# PowerSupply.net
KiCad netlist of a schematic drawn in Altium Designer
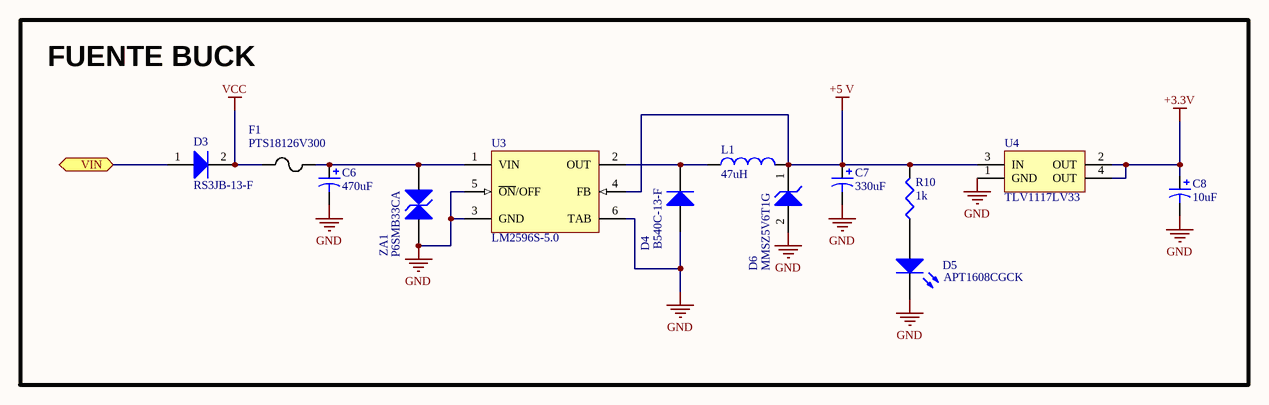
[diagram p0: PowerSupply.SchDoc]

(export (version "E")
  (design (tool "Eeschema 10.0.6"))
  (components
    (comp (ref "C6")
      (value "470uF")
      (footprint "CapElecSMD_10mm")
      (description "Polarized Capacitor (Surface Mount)")
      (fields (field (name "PUBLISHER") "Altium Limited"))
      (libsource (lib "Miscellaneous Devices") (part "Cap Pol3"))
    )
    (comp (ref "C7")
      (value "330uF")
      (footprint "CapElecSMD_8mm")
      (description "Polarized Capacitor (Surface Mount)")
      (fields (field (name "PUBLISHER") "Altium Limited"))
      (libsource (lib "Miscellaneous Devices") (part "Cap Pol3"))
    )
    (comp (ref "C8")
      (value "10uF")
      (footprint "CAPC3225N")
      (description "Polarized Capacitor (Surface Mount)")
      (fields (field (name "PUBLISHER") "Altium Limited"))
      (libsource (lib "Miscellaneous Devices") (part "Cap Pol3"))
    )
    (comp (ref "D3")
      (value "RS3JB-13-F")
      (footprint "MH_Miscellaneous_Devices_Pcblib:SMB")
      (description "Default Diode")
      (fields (field (name "PUBLISHER") "Altium Limited"))
      (libsource (lib "") (part "Diode_1"))
    )
    (comp (ref "D4")
      (value "B540C-13-F")
      (footprint "MH_Miscellaneous_Devices_Pcblib:SMC")
      (description "Default Diode")
      (fields (field (name "PUBLISHER") "Altium Limited"))
      (libsource (lib "Miscellaneous Devices") (part "Diode"))
    )
    (comp (ref "D5")
      (value "APT1608CGCK")
      (footprint "ChipDiode1608")
      (description "LED 1.6x0.8 mm 570 nm GRN CLR SMD")
      (fields (field (name "PUBLISHER") "Altium Limited"))
      (libsource (lib "Miscellaneous Devices") (part "LED2"))
    )
    (comp (ref "D6")
      (value "MMSZ5V6T1G")
      (footprint "SOD-123_ONS-M")
      (description "Zener Diode")
      (fields (field (name "PUBLISHER") "Altium Limited"))
      (libsource (lib "Miscellaneous Devices") (part "D Zener"))
    )
    (comp (ref "F1")
      (value "PTS18126V300")
      (footprint "FUSE_PTS18126_COB")
      (description "PTC RESET FUSE 6V 3A 1812")
      (libsource (lib "Adox_Lib") (part "PTS18126V300"))
    )
    (comp (ref "L1")
      (value "47uH")
      (footprint "INDUCTOR_47UH_3A")
      (description "Inductor")
      (fields (field (name "PUBLISHER") "Altium Limited"))
      (libsource (lib "Miscellaneous Devices") (part "Inductor"))
    )
    (comp (ref "R10")
      (value "1k")
      (footprint "RESC2012N")
      (description "Resistor")
      (fields (field (name "PUBLISHER") "Altium Limited"))
      (libsource (lib "Miscellaneous Devices") (part "Res3"))
    )
    (comp (ref "U3")
      (value "LM2596S-5.0")
      (footprint "LM2596S-5.0")
      (description "IC REG BUCK 5V 3A TO263-5L")
      (libsource (lib "MH_Lib") (part "LM2596S-5.0"))
    )
    (comp (ref "U4")
      (value "TLV1117LV33")
      (footprint "SOT223")
      (description "1-A, Positive Fixed Voltage, Low-Dropout Regulator")
      (libsource (lib "Adox_Lib") (part "TLV1117LV33"))
    )
    (comp (ref "ZA1")
      (value "P6SMB33CA")
      (footprint "MH_Miscellaneous_Devices_Pcblib:SMB")
      (description "Transient voltage suppressor diode")
      (libsource (lib "Adox_Lib") (part "TVS Diode"))
    )
  )
  (nets
    (net (code "1") (name "+3.3V") (class "Default")
      (node (ref "C8") (pin "1") (pinfunction "1_1") (pintype "passive"))
      (node (ref "U4") (pin "2") (pinfunction "OUT_2") (pintype "power_in"))
      (node (ref "U4") (pin "4") (pinfunction "OUT_4") (pintype "power_in"))
    )
    (net (code "2") (name "+5 V") (class "Default")
      (node (ref "C7") (pin "1") (pinfunction "1_1") (pintype "passive"))
      (node (ref "D6") (pin "1") (pinfunction "K_1") (pintype "passive"))
      (node (ref "L1") (pin "2") (pinfunction "2_2") (pintype "passive"))
      (node (ref "R10") (pin "2") (pinfunction "2_2") (pintype "passive"))
      (node (ref "U3") (pin "4") (pinfunction "FB_4") (pintype "input"))
      (node (ref "U4") (pin "3") (pinfunction "IN_3") (pintype "power_in"))
    )
    (net (code "3") (name "/VIN") (class "Default")
      (node (ref "D3") (pin "1") (pinfunction "A_1") (pintype "passive"))
    )
    (net (code "4") (name "GND") (class "Default")
      (node (ref "C6") (pin "2") (pinfunction "2_2") (pintype "passive"))
      (node (ref "C7") (pin "2") (pinfunction "2_2") (pintype "passive"))
      (node (ref "C8") (pin "2") (pinfunction "2_2") (pintype "passive"))
      (node (ref "D4") (pin "1") (pinfunction "A_1") (pintype "passive"))
      (node (ref "D5") (pin "2") (pinfunction "K_2") (pintype "passive"))
      (node (ref "D6") (pin "2") (pinfunction "A_2") (pintype "passive"))
      (node (ref "U3") (pin "3") (pinfunction "GND_3") (pintype "power_in"))
      (node (ref "U3") (pin "5") (pinfunction "~{ON}/OFF_5") (pintype "input"))
      (node (ref "U3") (pin "6") (pinfunction "TAB_6") (pintype "power_in"))
      (node (ref "U4") (pin "1") (pinfunction "GND_1") (pintype "power_in"))
      (node (ref "ZA1") (pin "2") (pinfunction "2_2") (pintype "passive"))
    )
    (net (code "5") (name "Net-(D4-K)") (class "Default")
      (node (ref "D4") (pin "2") (pinfunction "K_2") (pintype "passive"))
      (node (ref "L1") (pin "1") (pinfunction "1_1") (pintype "passive"))
      (node (ref "U3") (pin "2") (pinfunction "OUT_2") (pintype "power_in"))
    )
    (net (code "6") (name "Net-(D5-A)") (class "Default")
      (node (ref "D5") (pin "1") (pinfunction "A_1") (pintype "passive"))
      (node (ref "R10") (pin "1") (pinfunction "1_1") (pintype "passive"))
    )
    (net (code "7") (name "Net-(U3-VIN)") (class "Default")
      (node (ref "C6") (pin "1") (pinfunction "1_1") (pintype "passive"))
      (node (ref "F1") (pin "2") (pinfunction "2_2") (pintype "passive"))
      (node (ref "U3") (pin "1") (pinfunction "VIN_1") (pintype "power_in"))
      (node (ref "ZA1") (pin "1") (pinfunction "1_1") (pintype "passive"))
    )
    (net (code "8") (name "VCC") (class "Default")
      (node (ref "D3") (pin "2") (pinfunction "K_2") (pintype "passive"))
      (node (ref "F1") (pin "1") (pinfunction "1_1") (pintype "passive"))
    )
  )
)
